# untitled.net
KiCad netlist of a schematic drawn in EAGLE
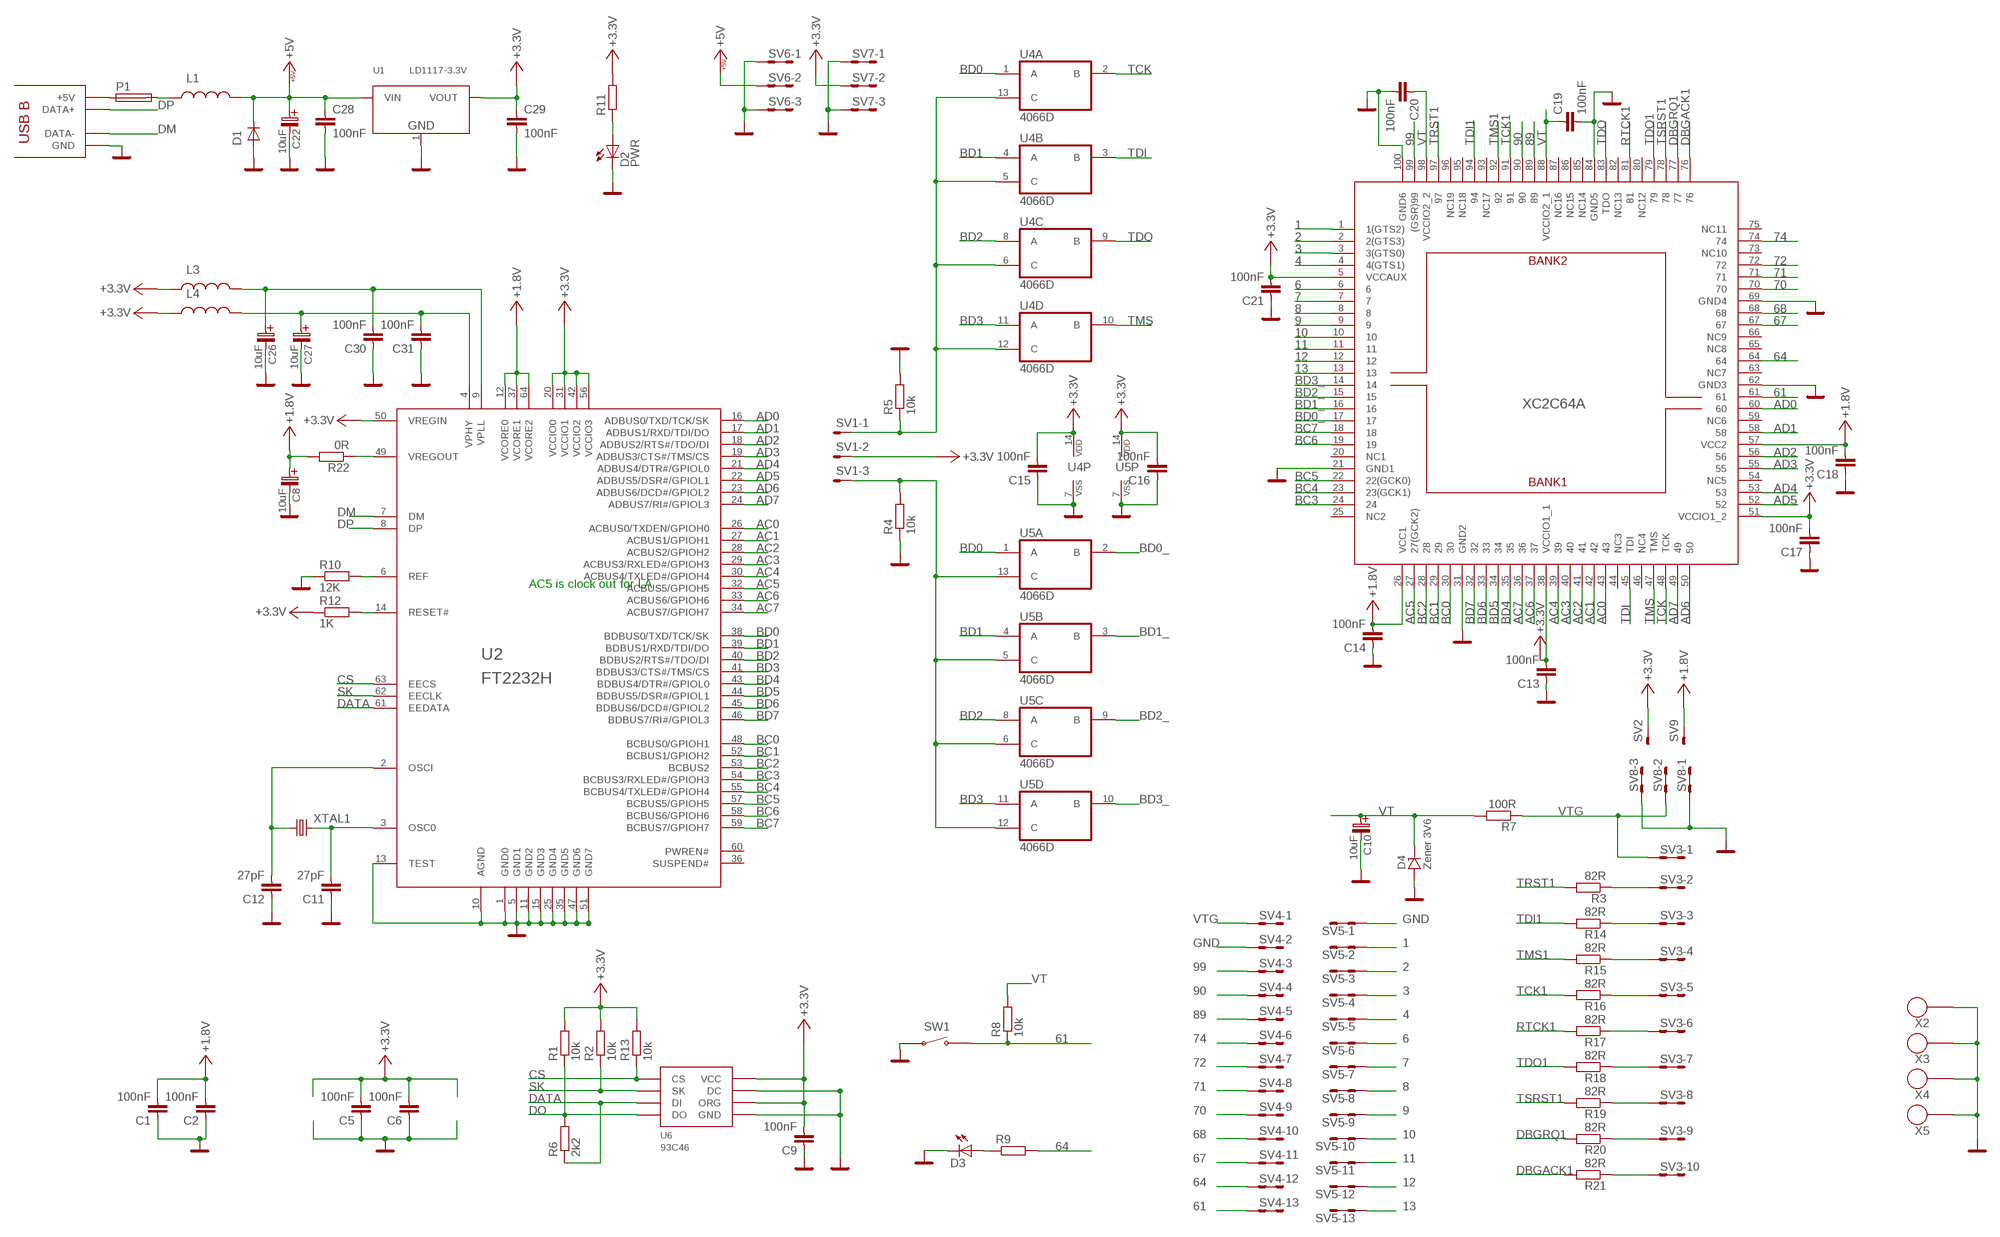
[diagram p0: schematic, sheet 1]

(export (version "E")
  (design (tool "Eeschema 10.0.6"))
  (components
    (comp (ref "C1")
      (value "100nF")
      (footprint "eagle-import:C0805")
      (libsource (lib "eagle-import") (part "C0805"))
    )
    (comp (ref "C2")
      (value "100nF")
      (footprint "eagle-import:C0805")
      (libsource (lib "eagle-import") (part "C0805"))
    )
    (comp (ref "C5")
      (value "100nF")
      (footprint "eagle-import:C0805")
      (libsource (lib "eagle-import") (part "C0805"))
    )
    (comp (ref "C6")
      (value "100nF")
      (footprint "eagle-import:C0805")
      (libsource (lib "eagle-import") (part "C0805"))
    )
    (comp (ref "C8") (value "10uF") (footprint "eagle-import:B") (libsource (lib "eagle-import") (part "B")))
    (comp (ref "C9")
      (value "100nF")
      (footprint "eagle-import:C0805")
      (libsource (lib "eagle-import") (part "C0805"))
    )
    (comp (ref "C10") (value "10uF") (footprint "eagle-import:B") (libsource (lib "eagle-import") (part "B")))
    (comp (ref "C11")
      (value "27pF")
      (footprint "eagle-import:C0805")
      (libsource (lib "eagle-import") (part "C0805"))
    )
    (comp (ref "C12")
      (value "27pF")
      (footprint "eagle-import:C0805")
      (libsource (lib "eagle-import") (part "C0805"))
    )
    (comp (ref "C13")
      (value "100nF")
      (footprint "eagle-import:C0805")
      (libsource (lib "eagle-import") (part "C0805"))
    )
    (comp (ref "C14")
      (value "100nF")
      (footprint "eagle-import:C0805")
      (libsource (lib "eagle-import") (part "C0805"))
    )
    (comp (ref "C15")
      (value "100nF")
      (footprint "eagle-import:C0805")
      (libsource (lib "eagle-import") (part "C0805"))
    )
    (comp (ref "C16")
      (value "100nF")
      (footprint "eagle-import:C0805")
      (libsource (lib "eagle-import") (part "C0805"))
    )
    (comp (ref "C17")
      (value "100nF")
      (footprint "eagle-import:C0805")
      (libsource (lib "eagle-import") (part "C0805"))
    )
    (comp (ref "C18")
      (value "100nF")
      (footprint "eagle-import:C0805")
      (libsource (lib "eagle-import") (part "C0805"))
    )
    (comp (ref "C19")
      (value "100nF")
      (footprint "eagle-import:C0805")
      (libsource (lib "eagle-import") (part "C0805"))
    )
    (comp (ref "C20")
      (value "100nF")
      (footprint "eagle-import:C0805")
      (libsource (lib "eagle-import") (part "C0805"))
    )
    (comp (ref "C21")
      (value "100nF")
      (footprint "eagle-import:C0805")
      (libsource (lib "eagle-import") (part "C0805"))
    )
    (comp (ref "C22") (value "10uF") (footprint "eagle-import:B") (libsource (lib "eagle-import") (part "B")))
    (comp (ref "C26") (value "10uF") (footprint "eagle-import:B") (libsource (lib "eagle-import") (part "B")))
    (comp (ref "C27") (value "10uF") (footprint "eagle-import:B") (libsource (lib "eagle-import") (part "B")))
    (comp (ref "C28")
      (value "100nF")
      (footprint "eagle-import:C0805")
      (libsource (lib "eagle-import") (part "C0805"))
    )
    (comp (ref "C29")
      (value "100nF")
      (footprint "eagle-import:C0805")
      (libsource (lib "eagle-import") (part "C0805"))
    )
    (comp (ref "C30")
      (value "100nF")
      (footprint "eagle-import:C0805")
      (libsource (lib "eagle-import") (part "C0805"))
    )
    (comp (ref "C31")
      (value "100nF")
      (footprint "eagle-import:C0805")
      (libsource (lib "eagle-import") (part "C0805"))
    )
    (comp (ref "D1")
      (value "D-OB.SMA")
      (footprint "eagle-import:SMA")
      (libsource (lib "eagle-import") (part "D-OB.SMA"))
    )
    (comp (ref "D2")
      (value "PWR")
      (footprint "eagle-import:1206")
      (libsource (lib "eagle-import") (part "LED1206"))
    )
    (comp (ref "D3")
      (value "LED1206")
      (footprint "eagle-import:1206")
      (libsource (lib "eagle-import") (part "LED1206"))
    )
    (comp (ref "D4")
      (value "Zener 3V6")
      (footprint "eagle-import:MINIMELF")
      (libsource (lib "eagle-import") (part "D-ZENEROVA"))
    )
    (comp (ref "L1")
      (value "L0805")
      (footprint "eagle-import:L0805")
      (libsource (lib "eagle-import") (part "L0805"))
    )
    (comp (ref "L3")
      (value "L1210")
      (footprint "eagle-import:1210")
      (libsource (lib "eagle-import") (part "L1210"))
    )
    (comp (ref "L4")
      (value "L1210")
      (footprint "eagle-import:1210")
      (libsource (lib "eagle-import") (part "L1210"))
    )
    (comp (ref "P1")
      (value "POJISTKA_1812")
      (footprint "eagle-import:1812")
      (libsource (lib "eagle-import") (part "POJISTKA_1812"))
    )
    (comp (ref "R1")
      (value "10k")
      (footprint "eagle-import:0805")
      (libsource (lib "eagle-import") (part "R0805"))
    )
    (comp (ref "R2")
      (value "10k")
      (footprint "eagle-import:0805")
      (libsource (lib "eagle-import") (part "R0805"))
    )
    (comp (ref "R3")
      (value "82R")
      (footprint "eagle-import:0805")
      (libsource (lib "eagle-import") (part "R0805"))
    )
    (comp (ref "R4")
      (value "10k")
      (footprint "eagle-import:0805")
      (libsource (lib "eagle-import") (part "R0805"))
    )
    (comp (ref "R5")
      (value "10k")
      (footprint "eagle-import:0805")
      (libsource (lib "eagle-import") (part "R0805"))
    )
    (comp (ref "R6")
      (value "2k2")
      (footprint "eagle-import:0805")
      (libsource (lib "eagle-import") (part "R0805"))
    )
    (comp (ref "R7")
      (value "100R")
      (footprint "eagle-import:0805")
      (libsource (lib "eagle-import") (part "R0805"))
    )
    (comp (ref "R8")
      (value "10k")
      (footprint "eagle-import:0805")
      (libsource (lib "eagle-import") (part "R0805"))
    )
    (comp (ref "R9")
      (value "R0805")
      (footprint "eagle-import:0805")
      (libsource (lib "eagle-import") (part "R0805"))
    )
    (comp (ref "R10")
      (value "12K")
      (footprint "eagle-import:0805")
      (libsource (lib "eagle-import") (part "R0805"))
    )
    (comp (ref "R11")
      (value "R0805")
      (footprint "eagle-import:0805")
      (libsource (lib "eagle-import") (part "R0805"))
    )
    (comp (ref "R12")
      (value "1K")
      (footprint "eagle-import:0805")
      (libsource (lib "eagle-import") (part "R0805"))
    )
    (comp (ref "R13")
      (value "10k")
      (footprint "eagle-import:0805")
      (libsource (lib "eagle-import") (part "R0805"))
    )
    (comp (ref "R14")
      (value "82R")
      (footprint "eagle-import:0805")
      (libsource (lib "eagle-import") (part "R0805"))
    )
    (comp (ref "R15")
      (value "82R")
      (footprint "eagle-import:0805")
      (libsource (lib "eagle-import") (part "R0805"))
    )
    (comp (ref "R16")
      (value "82R")
      (footprint "eagle-import:0805")
      (libsource (lib "eagle-import") (part "R0805"))
    )
    (comp (ref "R17")
      (value "82R")
      (footprint "eagle-import:0805")
      (libsource (lib "eagle-import") (part "R0805"))
    )
    (comp (ref "R18")
      (value "82R")
      (footprint "eagle-import:0805")
      (libsource (lib "eagle-import") (part "R0805"))
    )
    (comp (ref "R19")
      (value "82R")
      (footprint "eagle-import:0805")
      (libsource (lib "eagle-import") (part "R0805"))
    )
    (comp (ref "R20")
      (value "82R")
      (footprint "eagle-import:0805")
      (libsource (lib "eagle-import") (part "R0805"))
    )
    (comp (ref "R21")
      (value "82R")
      (footprint "eagle-import:0805")
      (libsource (lib "eagle-import") (part "R0805"))
    )
    (comp (ref "R22")
      (value "0R")
      (footprint "eagle-import:0805")
      (libsource (lib "eagle-import") (part "R0805"))
    )
    (comp (ref "SV1")
      (value "MA03-1")
      (footprint "eagle-import:MA03-1")
      (libsource (lib "eagle-import") (part "MA03-1"))
    )
    (comp (ref "SV2")
      (value "MA01-1")
      (footprint "eagle-import:MA01-1")
      (libsource (lib "eagle-import") (part "MA01-1"))
    )
    (comp (ref "SV3")
      (value "MA10-2")
      (footprint "eagle-import:MA10-2")
      (libsource (lib "eagle-import") (part "MA10-2"))
    )
    (comp (ref "SV4")
      (value "MA13-2")
      (footprint "eagle-import:MA13-2")
      (libsource (lib "eagle-import") (part "MA13-2"))
    )
    (comp (ref "SV5")
      (value "MA13-2")
      (footprint "eagle-import:MA13-2")
      (libsource (lib "eagle-import") (part "MA13-2"))
    )
    (comp (ref "SV6")
      (value "MA03-2")
      (footprint "eagle-import:MA03-2")
      (libsource (lib "eagle-import") (part "MA03-2"))
    )
    (comp (ref "SV7")
      (value "MA03-2")
      (footprint "eagle-import:MA03-2")
      (libsource (lib "eagle-import") (part "MA03-2"))
    )
    (comp (ref "SV8")
      (value "MA03-2")
      (footprint "eagle-import:MA03-2")
      (libsource (lib "eagle-import") (part "MA03-2"))
    )
    (comp (ref "SV9")
      (value "MA01-1")
      (footprint "eagle-import:MA01-1")
      (libsource (lib "eagle-import") (part "MA01-1"))
    )
    (comp (ref "SW1")
      (value "TACT-64K")
      (footprint "eagle-import:TACT-64K")
      (libsource (lib "eagle-import") (part "TACT-64K"))
    )
    (comp (ref "U1")
      (value "LD1117-3.3V")
      (footprint "eagle-import:SOT223")
      (libsource (lib "eagle-import") (part "LD1117-3.3SOT223"))
    )
    (comp (ref "U2")
      (value "FT2232H")
      (footprint "eagle-import:LQFP64")
      (libsource (lib "eagle-import") (part "FT2232H"))
    )
    (comp (ref "U3")
      (value "XC2C64A")
      (footprint "eagle-import:VQ100")
      (libsource (lib "eagle-import") (part "XC2C64A"))
    )
    (comp (ref "U4")
      (value "4066D")
      (footprint "eagle-import:SO14")
      (libsource (lib "eagle-import") (part "4066D"))
    )
    (comp (ref "U5")
      (value "4066D")
      (footprint "eagle-import:SO14")
      (libsource (lib "eagle-import") (part "4066D"))
    )
    (comp (ref "U6")
      (value "93C46")
      (footprint "eagle-import:SOIC8")
      (libsource (lib "eagle-import") (part "93C46"))
    )
    (comp (ref "X1")
      (value "USB_B")
      (footprint "eagle-import:USB_B")
      (libsource (lib "eagle-import") (part "USB_B"))
    )
    (comp (ref "X2")
      (value "SROUB3M")
      (footprint "eagle-import:SROUB3M")
      (libsource (lib "eagle-import") (part "SROUB3M"))
    )
    (comp (ref "X3")
      (value "SROUB3M")
      (footprint "eagle-import:SROUB3M")
      (libsource (lib "eagle-import") (part "SROUB3M"))
    )
    (comp (ref "X4")
      (value "SROUB3M")
      (footprint "eagle-import:SROUB3M")
      (libsource (lib "eagle-import") (part "SROUB3M"))
    )
    (comp (ref "X5")
      (value "SROUB3M")
      (footprint "eagle-import:SROUB3M")
      (libsource (lib "eagle-import") (part "SROUB3M"))
    )
    (comp (ref "XTAL1")
      (value "KRYSLAL_S49")
      (footprint "eagle-import:S49")
      (libsource (lib "eagle-import") (part "KRYSLAL_S49"))
    )
  )
  (nets
    (net (code "1") (name "+1.8V") (class "Default")
      (node (ref "C1") (pin "2") (pinfunction "2_2") (pintype "passive"))
      (node (ref "C14") (pin "2") (pinfunction "2_2") (pintype "passive"))
      (node (ref "C18") (pin "2") (pinfunction "2_2") (pintype "passive"))
      (node (ref "C2") (pin "2") (pinfunction "2_2") (pintype "passive"))
      (node (ref "C8") (pin "+") (pinfunction "C_EL+_+") (pintype "passive"))
      (node (ref "R22") (pin "2") (pinfunction "2_2") (pintype "passive"))
      (node (ref "SV9") (pin "1") (pinfunction "P$1_1") (pintype "passive"))
      (node (ref "U2") (pin "12") (pinfunction "VCORE0_12") (pintype "bidirectional"))
      (node (ref "U2") (pin "37") (pinfunction "VCORE1_37") (pintype "bidirectional"))
      (node (ref "U2") (pin "64") (pinfunction "VCORE2_64") (pintype "bidirectional"))
      (node (ref "U3") (pin "26") (pinfunction "VCC1_26") (pintype "bidirectional"))
      (node (ref "U3") (pin "57") (pinfunction "VCC2_57") (pintype "bidirectional"))
    )
    (net (code "2") (name "+3.3V") (class "Default")
      (node (ref "C13") (pin "2") (pinfunction "2_2") (pintype "passive"))
      (node (ref "C15") (pin "2") (pinfunction "2_2") (pintype "passive"))
      (node (ref "C16") (pin "2") (pinfunction "2_2") (pintype "passive"))
      (node (ref "C17") (pin "2") (pinfunction "2_2") (pintype "passive"))
      (node (ref "C21") (pin "2") (pinfunction "2_2") (pintype "passive"))
      (node (ref "C29") (pin "1") (pinfunction "1_1") (pintype "passive"))
      (node (ref "C5") (pin "2") (pinfunction "2_2") (pintype "passive"))
      (node (ref "C6") (pin "2") (pinfunction "2_2") (pintype "passive"))
      (node (ref "C9") (pin "2") (pinfunction "2_2") (pintype "passive"))
      (node (ref "L3") (pin "P$1") (pinfunction "1_P$1") (pintype "passive"))
      (node (ref "L4") (pin "P$1") (pinfunction "1_P$1") (pintype "passive"))
      (node (ref "R1") (pin "2") (pinfunction "2_2") (pintype "passive"))
      (node (ref "R11") (pin "2") (pinfunction "2_2") (pintype "passive"))
      (node (ref "R12") (pin "1") (pinfunction "1_1") (pintype "passive"))
      (node (ref "R13") (pin "2") (pinfunction "2_2") (pintype "passive"))
      (node (ref "R2") (pin "2") (pinfunction "2_2") (pintype "passive"))
      (node (ref "SV1") (pin "2") (pinfunction "P$1_2") (pintype "passive"))
      (node (ref "SV2") (pin "1") (pinfunction "P$1_1") (pintype "passive"))
      (node (ref "SV7") (pin "3") (pinfunction "K_3") (pintype "passive"))
      (node (ref "SV7") (pin "4") (pinfunction "K_4") (pintype "passive"))
      (node (ref "U1") (pin "2") (pinfunction "VOUT_2") (pintype "bidirectional"))
      (node (ref "U2") (pin "20") (pinfunction "VCCIO0_20") (pintype "bidirectional"))
      (node (ref "U2") (pin "31") (pinfunction "VCCIO1_31") (pintype "bidirectional"))
      (node (ref "U2") (pin "42") (pinfunction "VCCIO2_42") (pintype "bidirectional"))
      (node (ref "U2") (pin "50") (pinfunction "VREGIN_50") (pintype "bidirectional"))
      (node (ref "U2") (pin "56") (pinfunction "VCCIO3_56") (pintype "bidirectional"))
      (node (ref "U3") (pin "38") (pinfunction "VCCIO1_1_38") (pintype "bidirectional"))
      (node (ref "U3") (pin "5") (pinfunction "VCCAUX_5") (pintype "bidirectional"))
      (node (ref "U3") (pin "51") (pinfunction "VCCIO1_2_51") (pintype "bidirectional"))
      (node (ref "U4") (pin "14") (pinfunction "VDD_14") (pintype "power_in"))
      (node (ref "U5") (pin "14") (pinfunction "VDD_14") (pintype "power_in"))
      (node (ref "U6") (pin "6") (pinfunction "ORG_6") (pintype "bidirectional"))
      (node (ref "U6") (pin "8") (pinfunction "VCC_8") (pintype "bidirectional"))
    )
    (net (code "3") (name "+5V") (class "Default")
      (node (ref "C22") (pin "+") (pinfunction "C_EL+_+") (pintype "passive"))
      (node (ref "C28") (pin "1") (pinfunction "1_1") (pintype "passive"))
      (node (ref "D1") (pin "K") (pinfunction "C_K") (pintype "passive"))
      (node (ref "L1") (pin "2") (pinfunction "2_2") (pintype "passive"))
      (node (ref "SV6") (pin "3") (pinfunction "K_3") (pintype "passive"))
      (node (ref "SV6") (pin "4") (pinfunction "K_4") (pintype "passive"))
      (node (ref "U1") (pin "3") (pinfunction "VIN_3") (pintype "bidirectional"))
    )
    (net (code "4") (name "/1") (class "Default")
      (node (ref "SV5") (pin "3") (pinfunction "K_3") (pintype "passive"))
      (node (ref "SV5") (pin "4") (pinfunction "K_4") (pintype "passive"))
      (node (ref "U3") (pin "1") (pinfunction "1(GTS2)_1") (pintype "bidirectional"))
    )
    (net (code "5") (name "/2") (class "Default")
      (node (ref "SV5") (pin "5") (pinfunction "K_5") (pintype "passive"))
      (node (ref "SV5") (pin "6") (pinfunction "K_6") (pintype "passive"))
      (node (ref "U3") (pin "2") (pinfunction "2(GTS3)_2") (pintype "bidirectional"))
    )
    (net (code "6") (name "/3") (class "Default")
      (node (ref "SV5") (pin "7") (pinfunction "K_7") (pintype "passive"))
      (node (ref "SV5") (pin "8") (pinfunction "K_8") (pintype "passive"))
      (node (ref "U3") (pin "3") (pinfunction "3(GTS0)_3") (pintype "bidirectional"))
    )
    (net (code "7") (name "/4") (class "Default")
      (node (ref "SV5") (pin "10") (pinfunction "K_10") (pintype "passive"))
      (node (ref "SV5") (pin "9") (pinfunction "K_9") (pintype "passive"))
      (node (ref "U3") (pin "4") (pinfunction "4(GTS1)_4") (pintype "bidirectional"))
    )
    (net (code "8") (name "/6") (class "Default")
      (node (ref "SV5") (pin "11") (pinfunction "K_11") (pintype "passive"))
      (node (ref "SV5") (pin "12") (pinfunction "K_12") (pintype "passive"))
      (node (ref "U3") (pin "6") (pinfunction "6_6") (pintype "bidirectional"))
    )
    (net (code "9") (name "/7") (class "Default")
      (node (ref "SV5") (pin "13") (pinfunction "K_13") (pintype "passive"))
      (node (ref "SV5") (pin "14") (pinfunction "K_14") (pintype "passive"))
      (node (ref "U3") (pin "7") (pinfunction "7_7") (pintype "bidirectional"))
    )
    (net (code "10") (name "/8") (class "Default")
      (node (ref "SV5") (pin "15") (pinfunction "K_15") (pintype "passive"))
      (node (ref "SV5") (pin "16") (pinfunction "K_16") (pintype "passive"))
      (node (ref "U3") (pin "8") (pinfunction "8_8") (pintype "bidirectional"))
    )
    (net (code "11") (name "/9") (class "Default")
      (node (ref "SV5") (pin "17") (pinfunction "K_17") (pintype "passive"))
      (node (ref "SV5") (pin "18") (pinfunction "K_18") (pintype "passive"))
      (node (ref "U3") (pin "9") (pinfunction "9_9") (pintype "bidirectional"))
    )
    (net (code "12") (name "/10") (class "Default")
      (node (ref "SV5") (pin "19") (pinfunction "K_19") (pintype "passive"))
      (node (ref "SV5") (pin "20") (pinfunction "K_20") (pintype "passive"))
      (node (ref "U3") (pin "10") (pinfunction "10_10") (pintype "bidirectional"))
    )
    (net (code "13") (name "/11") (class "Default")
      (node (ref "SV5") (pin "21") (pinfunction "K_21") (pintype "passive"))
      (node (ref "SV5") (pin "22") (pinfunction "K_22") (pintype "passive"))
      (node (ref "U3") (pin "11") (pinfunction "11_11") (pintype "bidirectional"))
    )
    (net (code "14") (name "/12") (class "Default")
      (node (ref "SV5") (pin "23") (pinfunction "K_23") (pintype "passive"))
      (node (ref "SV5") (pin "24") (pinfunction "K_24") (pintype "passive"))
      (node (ref "U3") (pin "12") (pinfunction "12_12") (pintype "bidirectional"))
    )
    (net (code "15") (name "/13") (class "Default")
      (node (ref "SV5") (pin "25") (pinfunction "K_25") (pintype "passive"))
      (node (ref "SV5") (pin "26") (pinfunction "K_26") (pintype "passive"))
      (node (ref "U3") (pin "13") (pinfunction "13_13") (pintype "bidirectional"))
    )
    (net (code "16") (name "/61") (class "Default")
      (node (ref "R8") (pin "1") (pinfunction "1_1") (pintype "passive"))
      (node (ref "SV4") (pin "25") (pinfunction "K_25") (pintype "passive"))
      (node (ref "SV4") (pin "26") (pinfunction "K_26") (pintype "passive"))
      (node (ref "SW1") (pin "P$3") (pinfunction "P$2_P$3") (pintype "passive"))
      (node (ref "SW1") (pin "P$4") (pinfunction "P$2_P$4") (pintype "passive"))
      (node (ref "U3") (pin "61") (pinfunction "61_61") (pintype "bidirectional"))
    )
    (net (code "17") (name "/64") (class "Default")
      (node (ref "R9") (pin "2") (pinfunction "2_2") (pintype "passive"))
      (node (ref "SV4") (pin "23") (pinfunction "K_23") (pintype "passive"))
      (node (ref "SV4") (pin "24") (pinfunction "K_24") (pintype "passive"))
      (node (ref "U3") (pin "64") (pinfunction "64_64") (pintype "bidirectional"))
    )
    (net (code "18") (name "/67") (class "Default")
      (node (ref "SV4") (pin "21") (pinfunction "K_21") (pintype "passive"))
      (node (ref "SV4") (pin "22") (pinfunction "K_22") (pintype "passive"))
      (node (ref "U3") (pin "67") (pinfunction "67_67") (pintype "bidirectional"))
    )
    (net (code "19") (name "/68") (class "Default")
      (node (ref "SV4") (pin "19") (pinfunction "K_19") (pintype "passive"))
      (node (ref "SV4") (pin "20") (pinfunction "K_20") (pintype "passive"))
      (node (ref "U3") (pin "68") (pinfunction "68_68") (pintype "bidirectional"))
    )
    (net (code "20") (name "/70") (class "Default")
      (node (ref "SV4") (pin "17") (pinfunction "K_17") (pintype "passive"))
      (node (ref "SV4") (pin "18") (pinfunction "K_18") (pintype "passive"))
      (node (ref "U3") (pin "70") (pinfunction "70_70") (pintype "bidirectional"))
    )
    (net (code "21") (name "/71") (class "Default")
      (node (ref "SV4") (pin "15") (pinfunction "K_15") (pintype "passive"))
      (node (ref "SV4") (pin "16") (pinfunction "K_16") (pintype "passive"))
      (node (ref "U3") (pin "71") (pinfunction "71_71") (pintype "bidirectional"))
    )
    (net (code "22") (name "/72") (class "Default")
      (node (ref "SV4") (pin "13") (pinfunction "K_13") (pintype "passive"))
      (node (ref "SV4") (pin "14") (pinfunction "K_14") (pintype "passive"))
      (node (ref "U3") (pin "72") (pinfunction "72_72") (pintype "bidirectional"))
    )
    (net (code "23") (name "/74") (class "Default")
      (node (ref "SV4") (pin "11") (pinfunction "K_11") (pintype "passive"))
      (node (ref "SV4") (pin "12") (pinfunction "K_12") (pintype "passive"))
      (node (ref "U3") (pin "74") (pinfunction "74_74") (pintype "bidirectional"))
    )
    (net (code "24") (name "/89") (class "Default")
      (node (ref "SV4") (pin "10") (pinfunction "K_10") (pintype "passive"))
      (node (ref "SV4") (pin "9") (pinfunction "K_9") (pintype "passive"))
      (node (ref "U3") (pin "89") (pinfunction "89_89") (pintype "bidirectional"))
    )
    (net (code "25") (name "/90") (class "Default")
      (node (ref "SV4") (pin "7") (pinfunction "K_7") (pintype "passive"))
      (node (ref "SV4") (pin "8") (pinfunction "K_8") (pintype "passive"))
      (node (ref "U3") (pin "90") (pinfunction "90_90") (pintype "bidirectional"))
    )
    (net (code "26") (name "/99") (class "Default")
      (node (ref "SV4") (pin "5") (pinfunction "K_5") (pintype "passive"))
      (node (ref "SV4") (pin "6") (pinfunction "K_6") (pintype "passive"))
      (node (ref "U3") (pin "99") (pinfunction "(GSR)99_99") (pintype "bidirectional"))
    )
    (net (code "27") (name "/AC0") (class "Default")
      (node (ref "U2") (pin "26") (pinfunction "ACBUS0/TXDEN/GPIOH0_26") (pintype "bidirectional"))
      (node (ref "U3") (pin "43") (pinfunction "43_43") (pintype "bidirectional"))
    )
    (net (code "28") (name "/AC1") (class "Default")
      (node (ref "U2") (pin "27") (pinfunction "ACBUS1/GPIOH1_27") (pintype "bidirectional"))
      (node (ref "U3") (pin "42") (pinfunction "42_42") (pintype "bidirectional"))
    )
    (net (code "29") (name "/AC2") (class "Default")
      (node (ref "U2") (pin "28") (pinfunction "ACBUS2/GPIOH2_28") (pintype "bidirectional"))
      (node (ref "U3") (pin "41") (pinfunction "41_41") (pintype "bidirectional"))
    )
    (net (code "30") (name "/AC3") (class "Default")
      (node (ref "U2") (pin "29") (pinfunction "ACBUS3/RXLED#/GPIOH3_29") (pintype "bidirectional"))
      (node (ref "U3") (pin "40") (pinfunction "40_40") (pintype "bidirectional"))
    )
    (net (code "31") (name "/AC4") (class "Default")
      (node (ref "U2") (pin "30") (pinfunction "ACBUS4/TXLED#/GPIOH4_30") (pintype "bidirectional"))
      (node (ref "U3") (pin "39") (pinfunction "39_39") (pintype "bidirectional"))
    )
    (net (code "32") (name "/AC5") (class "Default")
      (node (ref "U2") (pin "32") (pinfunction "ACBUS5/GPIOH5_32") (pintype "bidirectional"))
      (node (ref "U3") (pin "27") (pinfunction "27(GCK2)_27") (pintype "bidirectional"))
    )
    (net (code "33") (name "/AC6") (class "Default")
      (node (ref "U2") (pin "33") (pinfunction "ACBUS6/GPIOH6_33") (pintype "bidirectional"))
      (node (ref "U3") (pin "37") (pinfunction "37_37") (pintype "bidirectional"))
    )
    (net (code "34") (name "/AC7") (class "Default")
      (node (ref "U2") (pin "34") (pinfunction "ACBUS7/GPIOH7_34") (pintype "bidirectional"))
      (node (ref "U3") (pin "36") (pinfunction "36_36") (pintype "bidirectional"))
    )
    (net (code "35") (name "/AD0") (class "Default")
      (node (ref "U2") (pin "16") (pinfunction "ADBUS0/TXD/TCK/SK_16") (pintype "bidirectional"))
      (node (ref "U3") (pin "60") (pinfunction "60_60") (pintype "bidirectional"))
    )
    (net (code "36") (name "/AD1") (class "Default")
      (node (ref "U2") (pin "17") (pinfunction "ADBUS1/RXD/TDI/DO_17") (pintype "bidirectional"))
      (node (ref "U3") (pin "58") (pinfunction "58_58") (pintype "bidirectional"))
    )
    (net (code "37") (name "/AD2") (class "Default")
      (node (ref "U2") (pin "18") (pinfunction "ADBUS2/RTS#/TDO/DI_18") (pintype "bidirectional"))
      (node (ref "U3") (pin "56") (pinfunction "56_56") (pintype "bidirectional"))
    )
    (net (code "38") (name "/AD3") (class "Default")
      (node (ref "U2") (pin "19") (pinfunction "ADBUS3/CTS#/TMS/CS_19") (pintype "bidirectional"))
      (node (ref "U3") (pin "55") (pinfunction "55_55") (pintype "bidirectional"))
    )
    (net (code "39") (name "/AD4") (class "Default")
      (node (ref "U2") (pin "21") (pinfunction "ADBUS4/DTR#/GPIOL0_21") (pintype "bidirectional"))
      (node (ref "U3") (pin "53") (pinfunction "53_53") (pintype "bidirectional"))
    )
    (net (code "40") (name "/AD5") (class "Default")
      (node (ref "U2") (pin "22") (pinfunction "ADBUS5/DSR#/GPIOL1_22") (pintype "bidirectional"))
      (node (ref "U3") (pin "52") (pinfunction "52_52") (pintype "bidirectional"))
    )
    (net (code "41") (name "/AD6") (class "Default")
      (node (ref "U2") (pin "23") (pinfunction "ADBUS6/DCD#/GPIOL2_23") (pintype "bidirectional"))
      (node (ref "U3") (pin "50") (pinfunction "50_50") (pintype "bidirectional"))
    )
    (net (code "42") (name "/AD7") (class "Default")
      (node (ref "U2") (pin "24") (pinfunction "ADBUS7/RI#/GPIOL3_24") (pintype "bidirectional"))
      (node (ref "U3") (pin "49") (pinfunction "49_49") (pintype "bidirectional"))
    )
    (net (code "43") (name "/BC0") (class "Default")
      (node (ref "U2") (pin "48") (pinfunction "BCBUS0/GPIOH1_48") (pintype "bidirectional"))
      (node (ref "U3") (pin "30") (pinfunction "30_30") (pintype "bidirectional"))
    )
    (net (code "44") (name "/BC1") (class "Default")
      (node (ref "U2") (pin "52") (pinfunction "BCBUS1/GPIOH2_52") (pintype "bidirectional"))
      (node (ref "U3") (pin "29") (pinfunction "29_29") (pintype "bidirectional"))
    )
    (net (code "45") (name "/BC2") (class "Default")
      (node (ref "U2") (pin "53") (pinfunction "BCBUS2_53") (pintype "bidirectional"))
      (node (ref "U3") (pin "28") (pinfunction "28_28") (pintype "bidirectional"))
    )
    (net (code "46") (name "/BC3") (class "Default")
      (node (ref "U2") (pin "54") (pinfunction "BCBUS3/RXLED#/GPIOH3_54") (pintype "bidirectional"))
      (node (ref "U3") (pin "24") (pinfunction "24_24") (pintype "bidirectional"))
    )
    (net (code "47") (name "/BC4") (class "Default")
      (node (ref "U2") (pin "55") (pinfunction "BCBUS4/TXLED#/GPIOH4_55") (pintype "bidirectional"))
      (node (ref "U3") (pin "23") (pinfunction "23(GCK1)_23") (pintype "bidirectional"))
    )
    (net (code "48") (name "/BC5") (class "Default")
      (node (ref "U2") (pin "57") (pinfunction "BCBUS5/GPIOH5_57") (pintype "bidirectional"))
      (node (ref "U3") (pin "22") (pinfunction "22(GCK0)_22") (pintype "bidirectional"))
    )
    (net (code "49") (name "/BC6") (class "Default")
      (node (ref "U2") (pin "58") (pinfunction "BCBUS6/GPIOH6_58") (pintype "bidirectional"))
      (node (ref "U3") (pin "19") (pinfunction "19_19") (pintype "bidirectional"))
    )
    (net (code "50") (name "/BC7") (class "Default")
      (node (ref "U2") (pin "59") (pinfunction "BCBUS7/GPIOH7_59") (pintype "bidirectional"))
      (node (ref "U3") (pin "18") (pinfunction "18_18") (pintype "bidirectional"))
    )
    (net (code "51") (name "/BD0") (class "Default")
      (node (ref "U2") (pin "38") (pinfunction "BDBUS0/TXD/TCK/SK_38") (pintype "bidirectional"))
      (node (ref "U4") (pin "1") (pinfunction "A_1") (pintype "tri_state"))
      (node (ref "U5") (pin "1") (pinfunction "A_1") (pintype "tri_state"))
    )
    (net (code "52") (name "/BD0_") (class "Default")
      (node (ref "U3") (pin "17") (pinfunction "17_17") (pintype "bidirectional"))
      (node (ref "U5") (pin "2") (pinfunction "B_2") (pintype "tri_state"))
    )
    (net (code "53") (name "/BD1") (class "Default")
      (node (ref "U2") (pin "39") (pinfunction "BDBUS1/RXD/TDI/DO_39") (pintype "bidirectional"))
      (node (ref "U4") (pin "4") (pinfunction "A_4") (pintype "tri_state"))
      (node (ref "U5") (pin "4") (pinfunction "A_4") (pintype "tri_state"))
    )
    (net (code "54") (name "/BD1_") (class "Default")
      (node (ref "U3") (pin "16") (pinfunction "16_16") (pintype "bidirectional"))
      (node (ref "U5") (pin "3") (pinfunction "B_3") (pintype "tri_state"))
    )
    (net (code "55") (name "/BD2") (class "Default")
      (node (ref "U2") (pin "40") (pinfunction "BDBUS2/RTS#/TDO/DI_40") (pintype "bidirectional"))
      (node (ref "U4") (pin "8") (pinfunction "A_8") (pintype "tri_state"))
      (node (ref "U5") (pin "8") (pinfunction "A_8") (pintype "tri_state"))
    )
    (net (code "56") (name "/BD2_") (class "Default")
      (node (ref "U3") (pin "15") (pinfunction "15_15") (pintype "bidirectional"))
      (node (ref "U5") (pin "9") (pinfunction "B_9") (pintype "tri_state"))
    )
    (net (code "57") (name "/BD3") (class "Default")
      (node (ref "U2") (pin "41") (pinfunction "BDBUS3/CTS#/TMS/CS_41") (pintype "bidirectional"))
      (node (ref "U4") (pin "11") (pinfunction "A_11") (pintype "tri_state"))
      (node (ref "U5") (pin "11") (pinfunction "A_11") (pintype "tri_state"))
    )
    (net (code "58") (name "/BD3_") (class "Default")
      (node (ref "U3") (pin "14") (pinfunction "14_14") (pintype "bidirectional"))
      (node (ref "U5") (pin "10") (pinfunction "B_10") (pintype "tri_state"))
    )
    (net (code "59") (name "/BD4") (class "Default")
      (node (ref "U2") (pin "43") (pinfunction "BDBUS4/DTR#/GPIOL0_43") (pintype "bidirectional"))
      (node (ref "U3") (pin "35") (pinfunction "35_35") (pintype "bidirectional"))
    )
    (net (code "60") (name "/BD5") (class "Default")
      (node (ref "U2") (pin "44") (pinfunction "BDBUS5/DSR#/GPIOL1_44") (pintype "bidirectional"))
      (node (ref "U3") (pin "34") (pinfunction "34_34") (pintype "bidirectional"))
    )
    (net (code "61") (name "/BD6") (class "Default")
      (node (ref "U2") (pin "45") (pinfunction "BDBUS6/DCD#/GPIOL2_45") (pintype "bidirectional"))
      (node (ref "U3") (pin "33") (pinfunction "33_33") (pintype "bidirectional"))
    )
    (net (code "62") (name "/BD7") (class "Default")
      (node (ref "U2") (pin "46") (pinfunction "BDBUS7/RI#/GPIOL3_46") (pintype "bidirectional"))
      (node (ref "U3") (pin "32") (pinfunction "32_32") (pintype "bidirectional"))
    )
    (net (code "63") (name "/CS") (class "Default")
      (node (ref "R13") (pin "1") (pinfunction "1_1") (pintype "passive"))
      (node (ref "U2") (pin "63") (pinfunction "EECS_63") (pintype "bidirectional"))
      (node (ref "U6") (pin "1") (pinfunction "CS_1") (pintype "bidirectional"))
    )
    (net (code "64") (name "/DATA") (class "Default")
      (node (ref "R6") (pin "1") (pinfunction "1_1") (pintype "passive"))
      (node (ref "U2") (pin "61") (pinfunction "EEDATA_61") (pintype "bidirectional"))
      (node (ref "U6") (pin "3") (pinfunction "DI_3") (pintype "bidirectional"))
    )
    (net (code "65") (name "/DBGACK1") (class "Default")
      (node (ref "R21") (pin "2") (pinfunction "2_2") (pintype "passive"))
      (node (ref "U3") (pin "76") (pinfunction "76_76") (pintype "bidirectional"))
    )
    (net (code "66") (name "/DBGRQ1") (class "Default")
      (node (ref "R20") (pin "2") (pinfunction "2_2") (pintype "passive"))
      (node (ref "U3") (pin "77") (pinfunction "77_77") (pintype "bidirectional"))
    )
    (net (code "67") (name "/DM") (class "Default")
      (node (ref "U2") (pin "7") (pinfunction "DM_7") (pintype "bidirectional"))
      (node (ref "X1") (pin "2") (pinfunction "DATA-_2") (pintype "bidirectional"))
    )
    (net (code "68") (name "/DO") (class "Default")
      (node (ref "R1") (pin "1") (pinfunction "1_1") (pintype "passive"))
      (node (ref "R6") (pin "2") (pinfunction "2_2") (pintype "passive"))
      (node (ref "U6") (pin "4") (pinfunction "DO_4") (pintype "bidirectional"))
    )
    (net (code "69") (name "/DP") (class "Default")
      (node (ref "U2") (pin "8") (pinfunction "DP_8") (pintype "bidirectional"))
      (node (ref "X1") (pin "3") (pinfunction "DATA+_3") (pintype "bidirectional"))
    )
    (net (code "70") (name "/RTCK1") (class "Default")
      (node (ref "R17") (pin "2") (pinfunction "2_2") (pintype "passive"))
      (node (ref "U3") (pin "81") (pinfunction "81_81") (pintype "bidirectional"))
    )
    (net (code "71") (name "/SK") (class "Default")
      (node (ref "R2") (pin "1") (pinfunction "1_1") (pintype "passive"))
      (node (ref "U2") (pin "62") (pinfunction "EECLK_62") (pintype "bidirectional"))
      (node (ref "U6") (pin "2") (pinfunction "SK_2") (pintype "bidirectional"))
    )
    (net (code "72") (name "/TCK") (class "Default")
      (node (ref "U3") (pin "48") (pinfunction "TCK_48") (pintype "bidirectional"))
      (node (ref "U4") (pin "2") (pinfunction "B_2") (pintype "tri_state"))
    )
    (net (code "73") (name "/TCK1") (class "Default")
      (node (ref "R16") (pin "2") (pinfunction "2_2") (pintype "passive"))
      (node (ref "U3") (pin "91") (pinfunction "91_91") (pintype "bidirectional"))
    )
    (net (code "74") (name "/TDI") (class "Default")
      (node (ref "U3") (pin "45") (pinfunction "TDI_45") (pintype "bidirectional"))
      (node (ref "U4") (pin "3") (pinfunction "B_3") (pintype "tri_state"))
    )
    (net (code "75") (name "/TDI1") (class "Default")
      (node (ref "R14") (pin "2") (pinfunction "2_2") (pintype "passive"))
      (node (ref "U3") (pin "94") (pinfunction "94_94") (pintype "bidirectional"))
    )
    (net (code "76") (name "/TDO") (class "Default")
      (node (ref "U3") (pin "83") (pinfunction "TDO_83") (pintype "bidirectional"))
      (node (ref "U4") (pin "9") (pinfunction "B_9") (pintype "tri_state"))
    )
    (net (code "77") (name "/TDO1") (class "Default")
      (node (ref "R18") (pin "2") (pinfunction "2_2") (pintype "passive"))
      (node (ref "U3") (pin "79") (pinfunction "79_79") (pintype "bidirectional"))
    )
    (net (code "78") (name "/TMS") (class "Default")
      (node (ref "U3") (pin "47") (pinfunction "TMS_47") (pintype "bidirectional"))
      (node (ref "U4") (pin "10") (pinfunction "B_10") (pintype "tri_state"))
    )
    (net (code "79") (name "/TMS1") (class "Default")
      (node (ref "R15") (pin "2") (pinfunction "2_2") (pintype "passive"))
      (node (ref "U3") (pin "92") (pinfunction "92_92") (pintype "bidirectional"))
    )
    (net (code "80") (name "/TRST1") (class "Default")
      (node (ref "R3") (pin "2") (pinfunction "2_2") (pintype "passive"))
      (node (ref "U3") (pin "97") (pinfunction "97_97") (pintype "bidirectional"))
    )
    (net (code "81") (name "/TSRST1") (class "Default")
      (node (ref "R19") (pin "2") (pinfunction "2_2") (pintype "passive"))
      (node (ref "U3") (pin "78") (pinfunction "78_78") (pintype "bidirectional"))
    )
    (net (code "82") (name "/VT") (class "Default")
      (node (ref "C10") (pin "+") (pinfunction "C_EL+_+") (pintype "passive"))
      (node (ref "C19") (pin "1") (pinfunction "1_1") (pintype "passive"))
      (node (ref "C20") (pin "1") (pinfunction "1_1") (pintype "passive"))
      (node (ref "D4") (pin "C") (pinfunction "K_C") (pintype "passive"))
      (node (ref "R7") (pin "2") (pinfunction "2_2") (pintype "passive"))
      (node (ref "R8") (pin "2") (pinfunction "2_2") (pintype "passive"))
      (node (ref "U3") (pin "88") (pinfunction "VCCIO2_1_88") (pintype "bidirectional"))
      (node (ref "U3") (pin "98") (pinfunction "VCCIO2_2_98") (pintype "bidirectional"))
    )
    (net (code "83") (name "/VTG") (class "Default")
      (node (ref "R7") (pin "1") (pinfunction "1_1") (pintype "passive"))
      (node (ref "SV3") (pin "1") (pinfunction "K_1") (pintype "passive"))
      (node (ref "SV3") (pin "2") (pinfunction "K_2") (pintype "passive"))
      (node (ref "SV4") (pin "1") (pinfunction "K_1") (pintype "passive"))
      (node (ref "SV4") (pin "2") (pinfunction "K_2") (pintype "passive"))
      (node (ref "SV8") (pin "3") (pinfunction "K_3") (pintype "passive"))
      (node (ref "SV8") (pin "4") (pinfunction "K_4") (pintype "passive"))
    )
    (net (code "84") (name "GND") (class "Default")
      (node (ref "C1") (pin "1") (pinfunction "1_1") (pintype "passive"))
      (node (ref "C10") (pin "-") (pinfunction "C_EL-_-") (pintype "passive"))
      (node (ref "C11") (pin "1") (pinfunction "1_1") (pintype "passive"))
      (node (ref "C12") (pin "1") (pinfunction "1_1") (pintype "passive"))
      (node (ref "C13") (pin "1") (pinfunction "1_1") (pintype "passive"))
      (node (ref "C14") (pin "1") (pinfunction "1_1") (pintype "passive"))
      (node (ref "C15") (pin "1") (pinfunction "1_1") (pintype "passive"))
      (node (ref "C16") (pin "1") (pinfunction "1_1") (pintype "passive"))
      (node (ref "C17") (pin "1") (pinfunction "1_1") (pintype "passive"))
      (node (ref "C18") (pin "1") (pinfunction "1_1") (pintype "passive"))
      (node (ref "C19") (pin "2") (pinfunction "2_2") (pintype "passive"))
      (node (ref "C2") (pin "1") (pinfunction "1_1") (pintype "passive"))
      (node (ref "C20") (pin "2") (pinfunction "2_2") (pintype "passive"))
      (node (ref "C21") (pin "1") (pinfunction "1_1") (pintype "passive"))
      (node (ref "C22") (pin "-") (pinfunction "C_EL-_-") (pintype "passive"))
      (node (ref "C26") (pin "-") (pinfunction "C_EL-_-") (pintype "passive"))
      (node (ref "C27") (pin "-") (pinfunction "C_EL-_-") (pintype "passive"))
      (node (ref "C28") (pin "2") (pinfunction "2_2") (pintype "passive"))
      (node (ref "C29") (pin "2") (pinfunction "2_2") (pintype "passive"))
      (node (ref "C30") (pin "1") (pinfunction "1_1") (pintype "passive"))
      (node (ref "C31") (pin "1") (pinfunction "1_1") (pintype "passive"))
      (node (ref "C5") (pin "1") (pinfunction "1_1") (pintype "passive"))
      (node (ref "C6") (pin "1") (pinfunction "1_1") (pintype "passive"))
      (node (ref "C8") (pin "-") (pinfunction "C_EL-_-") (pintype "passive"))
      (node (ref "C9") (pin "1") (pinfunction "1_1") (pintype "passive"))
      (node (ref "D1") (pin "A") (pinfunction "A_A") (pintype "passive"))
      (node (ref "D2") (pin "K") (pinfunction "C_K") (pintype "passive"))
      (node (ref "D3") (pin "K") (pinfunction "C_K") (pintype "passive"))
      (node (ref "D4") (pin "A") (pinfunction "A_A") (pintype "passive"))
      (node (ref "R10") (pin "1") (pinfunction "1_1") (pintype "passive"))
      (node (ref "R4") (pin "1") (pinfunction "1_1") (pintype "passive"))
      (node (ref "R5") (pin "2") (pinfunction "2_2") (pintype "passive"))
      (node (ref "SV4") (pin "3") (pinfunction "K_3") (pintype "passive"))
      (node (ref "SV4") (pin "4") (pinfunction "K_4") (pintype "passive"))
      (node (ref "SV5") (pin "1") (pinfunction "K_1") (pintype "passive"))
      (node (ref "SV5") (pin "2") (pinfunction "K_2") (pintype "passive"))
      (node (ref "SV6") (pin "1") (pinfunction "K_1") (pintype "passive"))
      (node (ref "SV6") (pin "2") (pinfunction "K_2") (pintype "passive"))
      (node (ref "SV6") (pin "5") (pinfunction "K_5") (pintype "passive"))
      (node (ref "SV6") (pin "6") (pinfunction "K_6") (pintype "passive"))
      (node (ref "SV7") (pin "1") (pinfunction "K_1") (pintype "passive"))
      (node (ref "SV7") (pin "2") (pinfunction "K_2") (pintype "passive"))
      (node (ref "SV7") (pin "5") (pinfunction "K_5") (pintype "passive"))
      (node (ref "SV7") (pin "6") (pinfunction "K_6") (pintype "passive"))
      (node (ref "SV8") (pin "1") (pinfunction "K_1") (pintype "passive"))
      (node (ref "SV8") (pin "2") (pinfunction "K_2") (pintype "passive"))
      (node (ref "SV8") (pin "5") (pinfunction "K_5") (pintype "passive"))
      (node (ref "SV8") (pin "6") (pinfunction "K_6") (pintype "passive"))
      (node (ref "SW1") (pin "P$1") (pinfunction "P$1_P$1") (pintype "passive"))
      (node (ref "SW1") (pin "P$2") (pinfunction "P$1_P$2") (pintype "passive"))
      (node (ref "U1") (pin "1") (pinfunction "GND_1") (pintype "bidirectional"))
      (node (ref "U2") (pin "1") (pinfunction "GND0_1") (pintype "bidirectional"))
      (node (ref "U2") (pin "10") (pinfunction "AGND_10") (pintype "bidirectional"))
      (node (ref "U2") (pin "11") (pinfunction "GND2_11") (pintype "bidirectional"))
      (node (ref "U2") (pin "13") (pinfunction "TEST_13") (pintype "bidirectional"))
      (node (ref "U2") (pin "15") (pinfunction "GND3_15") (pintype "bidirectional"))
      (node (ref "U2") (pin "25") (pinfunction "GND4_25") (pintype "bidirectional"))
      (node (ref "U2") (pin "35") (pinfunction "GND5_35") (pintype "bidirectional"))
      (node (ref "U2") (pin "47") (pinfunction "GND6_47") (pintype "bidirectional"))
      (node (ref "U2") (pin "5") (pinfunction "GND1_5") (pintype "bidirectional"))
      (node (ref "U2") (pin "51") (pinfunction "GND7_51") (pintype "bidirectional"))
      (node (ref "U3") (pin "100") (pinfunction "GND6_100") (pintype "bidirectional"))
      (node (ref "U3") (pin "21") (pinfunction "GND1_21") (pintype "bidirectional"))
      (node (ref "U3") (pin "31") (pinfunction "GND2_31") (pintype "bidirectional"))
      (node (ref "U3") (pin "62") (pinfunction "GND3_62") (pintype "bidirectional"))
      (node (ref "U3") (pin "69") (pinfunction "GND4_69") (pintype "bidirectional"))
      (node (ref "U3") (pin "84") (pinfunction "GND5_84") (pintype "bidirectional"))
      (node (ref "U4") (pin "7") (pinfunction "VSS_7") (pintype "power_in"))
      (node (ref "U5") (pin "7") (pinfunction "VSS_7") (pintype "power_in"))
      (node (ref "U6") (pin "5") (pinfunction "GND_5") (pintype "bidirectional"))
      (node (ref "U6") (pin "7") (pinfunction "DC_7") (pintype "bidirectional"))
      (node (ref "X1") (pin "4") (pinfunction "GND_4") (pintype "bidirectional"))
      (node (ref "X1") (pin "GND") (pinfunction "GND_GND") (pintype "bidirectional"))
      (node (ref "X1") (pin "GND2") (pinfunction "GND_GND2") (pintype "bidirectional"))
      (node (ref "X2") (pin "P$1") (pinfunction "P$1_P$1") (pintype "bidirectional"))
      (node (ref "X3") (pin "P$1") (pinfunction "P$1_P$1") (pintype "bidirectional"))
      (node (ref "X4") (pin "P$1") (pinfunction "P$1_P$1") (pintype "bidirectional"))
      (node (ref "X5") (pin "P$1") (pinfunction "P$1_P$1") (pintype "bidirectional"))
    )
    (net (code "85") (name "Net-(C26-C_EL+)") (class "Default")
      (node (ref "C26") (pin "+") (pinfunction "C_EL+_+") (pintype "passive"))
      (node (ref "C30") (pin "2") (pinfunction "2_2") (pintype "passive"))
      (node (ref "L3") (pin "P$2") (pinfunction "2_P$2") (pintype "passive"))
      (node (ref "U2") (pin "9") (pinfunction "VPLL_9") (pintype "bidirectional"))
    )
    (net (code "86") (name "Net-(C27-C_EL+)") (class "Default")
      (node (ref "C27") (pin "+") (pinfunction "C_EL+_+") (pintype "passive"))
      (node (ref "C31") (pin "2") (pinfunction "2_2") (pintype "passive"))
      (node (ref "L4") (pin "P$2") (pinfunction "2_P$2") (pintype "passive"))
      (node (ref "U2") (pin "4") (pinfunction "VPHY_4") (pintype "bidirectional"))
    )
    (net (code "87") (name "Net-(D2-PadA)") (class "Default")
      (node (ref "D2") (pin "A") (pinfunction "A_A") (pintype "passive"))
      (node (ref "R11") (pin "1") (pinfunction "1_1") (pintype "passive"))
    )
    (net (code "88") (name "Net-(D3-PadA)") (class "Default")
      (node (ref "D3") (pin "A") (pinfunction "A_A") (pintype "passive"))
      (node (ref "R9") (pin "1") (pinfunction "1_1") (pintype "passive"))
    )
    (net (code "89") (name "Net-(L1-Pad1)") (class "Default")
      (node (ref "L1") (pin "1") (pinfunction "1_1") (pintype "passive"))
      (node (ref "P1") (pin "2") (pinfunction "2_2") (pintype "passive"))
    )
    (net (code "90") (name "Net-(R3-Pad1)") (class "Default")
      (node (ref "R3") (pin "1") (pinfunction "1_1") (pintype "passive"))
      (node (ref "SV3") (pin "3") (pinfunction "K_3") (pintype "passive"))
      (node (ref "SV3") (pin "4") (pinfunction "K_4") (pintype "passive"))
    )
    (net (code "91") (name "Net-(R14-Pad1)") (class "Default")
      (node (ref "R14") (pin "1") (pinfunction "1_1") (pintype "passive"))
      (node (ref "SV3") (pin "5") (pinfunction "K_5") (pintype "passive"))
      (node (ref "SV3") (pin "6") (pinfunction "K_6") (pintype "passive"))
    )
    (net (code "92") (name "Net-(R15-Pad1)") (class "Default")
      (node (ref "R15") (pin "1") (pinfunction "1_1") (pintype "passive"))
      (node (ref "SV3") (pin "7") (pinfunction "K_7") (pintype "passive"))
      (node (ref "SV3") (pin "8") (pinfunction "K_8") (pintype "passive"))
    )
    (net (code "93") (name "Net-(R16-Pad1)") (class "Default")
      (node (ref "R16") (pin "1") (pinfunction "1_1") (pintype "passive"))
      (node (ref "SV3") (pin "10") (pinfunction "K_10") (pintype "passive"))
      (node (ref "SV3") (pin "9") (pinfunction "K_9") (pintype "passive"))
    )
    (net (code "94") (name "Net-(R17-Pad1)") (class "Default")
      (node (ref "R17") (pin "1") (pinfunction "1_1") (pintype "passive"))
      (node (ref "SV3") (pin "11") (pinfunction "K_11") (pintype "passive"))
      (node (ref "SV3") (pin "12") (pinfunction "K_12") (pintype "passive"))
    )
    (net (code "95") (name "Net-(R18-Pad1)") (class "Default")
      (node (ref "R18") (pin "1") (pinfunction "1_1") (pintype "passive"))
      (node (ref "SV3") (pin "13") (pinfunction "K_13") (pintype "passive"))
      (node (ref "SV3") (pin "14") (pinfunction "K_14") (pintype "passive"))
    )
    (net (code "96") (name "Net-(R19-Pad1)") (class "Default")
      (node (ref "R19") (pin "1") (pinfunction "1_1") (pintype "passive"))
      (node (ref "SV3") (pin "15") (pinfunction "K_15") (pintype "passive"))
      (node (ref "SV3") (pin "16") (pinfunction "K_16") (pintype "passive"))
    )
    (net (code "97") (name "Net-(R20-Pad1)") (class "Default")
      (node (ref "R20") (pin "1") (pinfunction "1_1") (pintype "passive"))
      (node (ref "SV3") (pin "17") (pinfunction "K_17") (pintype "passive"))
      (node (ref "SV3") (pin "18") (pinfunction "K_18") (pintype "passive"))
    )
    (net (code "98") (name "Net-(R21-Pad1)") (class "Default")
      (node (ref "R21") (pin "1") (pinfunction "1_1") (pintype "passive"))
      (node (ref "SV3") (pin "19") (pinfunction "K_19") (pintype "passive"))
      (node (ref "SV3") (pin "20") (pinfunction "K_20") (pintype "passive"))
    )
    (net (code "99") (name "Net-(SV1A-P$1)") (class "Default")
      (node (ref "R5") (pin "1") (pinfunction "1_1") (pintype "passive"))
      (node (ref "SV1") (pin "1") (pinfunction "P$1_1") (pintype "passive"))
      (node (ref "U4") (pin "12") (pinfunction "C_12") (pintype "input"))
      (node (ref "U4") (pin "13") (pinfunction "C_13") (pintype "input"))
      (node (ref "U4") (pin "5") (pinfunction "C_5") (pintype "input"))
      (node (ref "U4") (pin "6") (pinfunction "C_6") (pintype "input"))
    )
    (net (code "100") (name "Net-(SV1C-P$1)") (class "Default")
      (node (ref "R4") (pin "2") (pinfunction "2_2") (pintype "passive"))
      (node (ref "SV1") (pin "3") (pinfunction "P$1_3") (pintype "passive"))
      (node (ref "U5") (pin "12") (pinfunction "C_12") (pintype "input"))
      (node (ref "U5") (pin "13") (pinfunction "C_13") (pintype "input"))
      (node (ref "U5") (pin "5") (pinfunction "C_5") (pintype "input"))
      (node (ref "U5") (pin "6") (pinfunction "C_6") (pintype "input"))
    )
    (net (code "101") (name "Net-(U2-OSC0)") (class "Default")
      (node (ref "C11") (pin "2") (pinfunction "2_2") (pintype "passive"))
      (node (ref "U2") (pin "3") (pinfunction "OSC0_3") (pintype "bidirectional"))
      (node (ref "XTAL1") (pin "P$2") (pinfunction "2_P$2") (pintype "passive"))
    )
    (net (code "102") (name "Net-(U2-OSCI)") (class "Default")
      (node (ref "C12") (pin "2") (pinfunction "2_2") (pintype "passive"))
      (node (ref "U2") (pin "2") (pinfunction "OSCI_2") (pintype "bidirectional"))
      (node (ref "XTAL1") (pin "P$1") (pinfunction "1_P$1") (pintype "passive"))
    )
    (net (code "103") (name "Net-(U2-REF)") (class "Default")
      (node (ref "R10") (pin "2") (pinfunction "2_2") (pintype "passive"))
      (node (ref "U2") (pin "6") (pinfunction "REF_6") (pintype "bidirectional"))
    )
    (net (code "104") (name "Net-(U2-RESET#)") (class "Default")
      (node (ref "R12") (pin "2") (pinfunction "2_2") (pintype "passive"))
      (node (ref "U2") (pin "14") (pinfunction "RESET#_14") (pintype "bidirectional"))
    )
    (net (code "105") (name "Net-(U2-VREGOUT)") (class "Default")
      (node (ref "R22") (pin "1") (pinfunction "1_1") (pintype "passive"))
      (node (ref "U2") (pin "49") (pinfunction "VREGOUT_49") (pintype "bidirectional"))
    )
    (net (code "106") (name "Net-(X1-+5V)") (class "Default")
      (node (ref "P1") (pin "1") (pinfunction "1_1") (pintype "passive"))
      (node (ref "X1") (pin "1") (pinfunction "+5V_1") (pintype "bidirectional"))
    )
    (net (code "107") (name "unconnected-(U2-PWREN#-Pad60)") (class "Default")
      (node (ref "U2") (pin "60") (pinfunction "PWREN#_60") (pintype "bidirectional"))
    )
    (net (code "108") (name "unconnected-(U2-SUSPEND#-Pad36)") (class "Default")
      (node (ref "U2") (pin "36") (pinfunction "SUSPEND#_36") (pintype "bidirectional"))
    )
    (net (code "109") (name "unconnected-(U3-NC1-Pad20)") (class "Default")
      (node (ref "U3") (pin "20") (pinfunction "NC1_20") (pintype "bidirectional"))
    )
    (net (code "110") (name "unconnected-(U3-NC2-Pad25)") (class "Default")
      (node (ref "U3") (pin "25") (pinfunction "NC2_25") (pintype "bidirectional"))
    )
    (net (code "111") (name "unconnected-(U3-NC3-Pad44)") (class "Default")
      (node (ref "U3") (pin "44") (pinfunction "NC3_44") (pintype "bidirectional"))
    )
    (net (code "112") (name "unconnected-(U3-NC4-Pad46)") (class "Default")
      (node (ref "U3") (pin "46") (pinfunction "NC4_46") (pintype "bidirectional"))
    )
    (net (code "113") (name "unconnected-(U3-NC5-Pad54)") (class "Default")
      (node (ref "U3") (pin "54") (pinfunction "NC5_54") (pintype "bidirectional"))
    )
    (net (code "114") (name "unconnected-(U3-NC6-Pad59)") (class "Default")
      (node (ref "U3") (pin "59") (pinfunction "NC6_59") (pintype "bidirectional"))
    )
    (net (code "115") (name "unconnected-(U3-NC7-Pad63)") (class "Default")
      (node (ref "U3") (pin "63") (pinfunction "NC7_63") (pintype "bidirectional"))
    )
    (net (code "116") (name "unconnected-(U3-NC8-Pad65)") (class "Default")
      (node (ref "U3") (pin "65") (pinfunction "NC8_65") (pintype "bidirectional"))
    )
    (net (code "117") (name "unconnected-(U3-NC9-Pad66)") (class "Default")
      (node (ref "U3") (pin "66") (pinfunction "NC9_66") (pintype "bidirectional"))
    )
    (net (code "118") (name "unconnected-(U3-NC10-Pad73)") (class "Default")
      (node (ref "U3") (pin "73") (pinfunction "NC10_73") (pintype "bidirectional"))
    )
    (net (code "119") (name "unconnected-(U3-NC11-Pad75)") (class "Default")
      (node (ref "U3") (pin "75") (pinfunction "NC11_75") (pintype "bidirectional"))
    )
    (net (code "120") (name "unconnected-(U3-NC12-Pad80)") (class "Default")
      (node (ref "U3") (pin "80") (pinfunction "NC12_80") (pintype "bidirectional"))
    )
    (net (code "121") (name "unconnected-(U3-NC13-Pad82)") (class "Default")
      (node (ref "U3") (pin "82") (pinfunction "NC13_82") (pintype "bidirectional"))
    )
    (net (code "122") (name "unconnected-(U3-NC14-Pad85)") (class "Default")
      (node (ref "U3") (pin "85") (pinfunction "NC14_85") (pintype "bidirectional"))
    )
    (net (code "123") (name "unconnected-(U3-NC15-Pad86)") (class "Default")
      (node (ref "U3") (pin "86") (pinfunction "NC15_86") (pintype "bidirectional"))
    )
    (net (code "124") (name "unconnected-(U3-NC16-Pad87)") (class "Default")
      (node (ref "U3") (pin "87") (pinfunction "NC16_87") (pintype "bidirectional"))
    )
    (net (code "125") (name "unconnected-(U3-NC17-Pad93)") (class "Default")
      (node (ref "U3") (pin "93") (pinfunction "NC17_93") (pintype "bidirectional"))
    )
    (net (code "126") (name "unconnected-(U3-NC18-Pad95)") (class "Default")
      (node (ref "U3") (pin "95") (pinfunction "NC18_95") (pintype "bidirectional"))
    )
    (net (code "127") (name "unconnected-(U3-NC19-Pad96)") (class "Default")
      (node (ref "U3") (pin "96") (pinfunction "NC19_96") (pintype "bidirectional"))
    )
  )
)
